# Syntheseproject_Elektronisch_Schema_2025.net
KiCad netlist of a schematic drawn in EasyEDA Pro
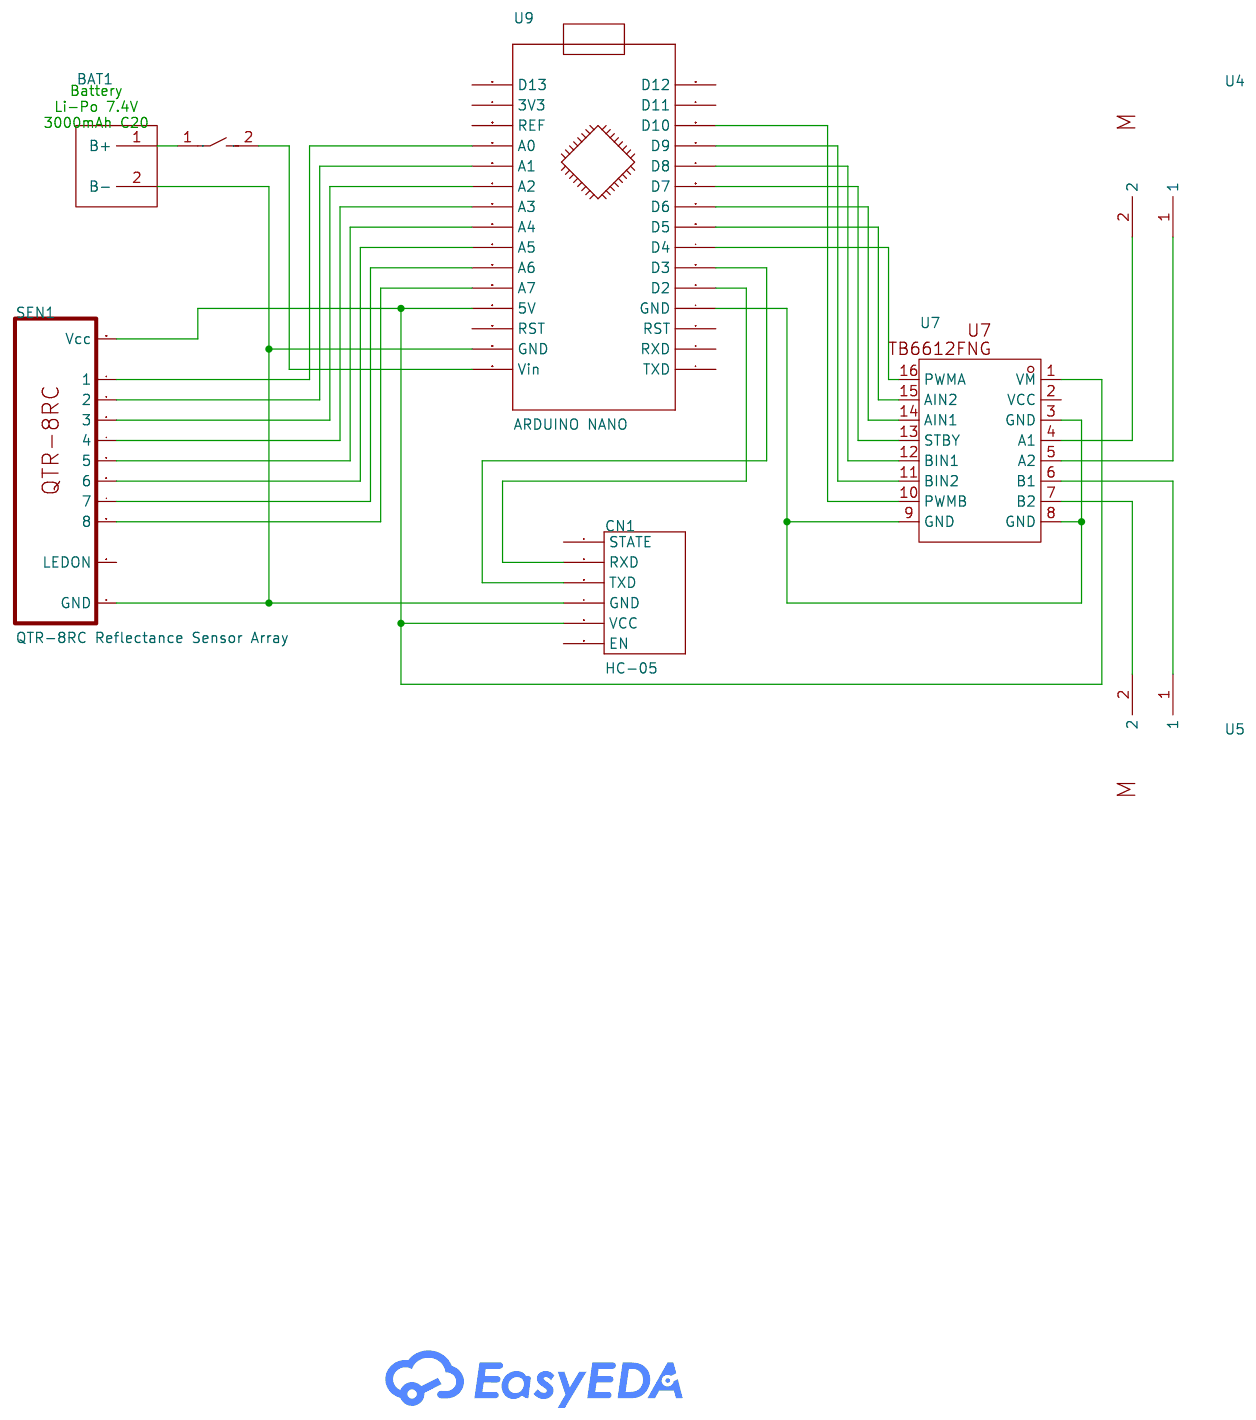
[diagram p0: schematic sheet]

(export (version "E")
  (design (tool "Eeschema 10.0.6"))
  (components
    (comp (ref "BAT1")
      (value "LiPo_7.4V_3000mAh_C20")
      (libsource (lib "easyedapro") (part "Battery_LiPo_7.4V_3000mAh"))
    )
    (comp (ref "CN1")
      (value "HC-05")
      (footprint "easyedapro:H6-2.54")
      (description "DIP-Black-Female-Header-VERT(6P)")
      (fields (field (name "Manufacturer Part") "F185-1106A1BSYC1"))
      (libsource (lib "easyedapro") (part "HC-05"))
    )
    (comp (ref "SEN1")
      (value "QTR-8RC Reflectance Sensor Array")
      (footprint "easyedapro:QTR-8X")
      (fields (field (name "Manufacturer") "Pololu"))
      (libsource (lib "easyedapro") (part "QTR-8RC Reflectance Sensor Array"))
    )
    (comp (ref "U4") (value "DC-MOTOR-GA12-N20") (libsource (lib "easyedapro") (part "DC-MOTOR-GA12-N20")))
    (comp (ref "U5") (value "DC-MOTOR-GA12-N20") (libsource (lib "easyedapro") (part "DC-MOTOR-GA12-N20")))
    (comp (ref "U7")
      (value "TB6612FNG SPARKFUN")
      (footprint "easyedapro:TB6612FNG")
      (fields (field (name "Manufacturer Part") "TB6612FNG"))
      (libsource (lib "easyedapro") (part "TB6612FNG SPARKFUN"))
    )
    (comp (ref "U8")
      (value "02-48-03-0004-00")
      (footprint "easyedapro:KEY-SMD_L6.0-W3.5-LS8.0-1")
      (libsource (lib "easyedapro") (part "02-48-03-0004-00"))
    )
    (comp (ref "U9")
      (value "ARDUINO NANO")
      (fields (field (name "Manufacturer Part") "?"))
      (libsource (lib "easyedapro") (part "ARDUINO NANO"))
    )
  )
  (nets
    (net (code "1") (name "Net-(BAT1-B+)") (class "Default")
      (node (ref "BAT1") (pin "1") (pinfunction "B+_1") (pintype "input"))
      (node (ref "U8") (pin "1") (pinfunction "1_1") (pintype "unspecified"))
    )
    (net (code "2") (name "Net-(BAT1-B-)") (class "Default")
      (node (ref "BAT1") (pin "2") (pinfunction "B-_2") (pintype "input"))
      (node (ref "CN1") (pin "4") (pinfunction "GND_4") (pintype "input"))
      (node (ref "SEN1") (pin "11") (pinfunction "GND_11") (pintype "unspecified"))
      (node (ref "U9") (pin "29") (pinfunction "GND_29") (pintype "unspecified"))
    )
    (net (code "3") (name "Net-(CN1-RXD)") (class "Default")
      (node (ref "CN1") (pin "2") (pinfunction "RXD_2") (pintype "input"))
      (node (ref "U9") (pin "5") (pinfunction "D2_5") (pintype "unspecified"))
    )
    (net (code "4") (name "Net-(CN1-TXD)") (class "Default")
      (node (ref "CN1") (pin "3") (pinfunction "TXD_3") (pintype "input"))
      (node (ref "U9") (pin "6") (pinfunction "D3_6") (pintype "unspecified"))
    )
    (net (code "5") (name "Net-(CN1-VCC)") (class "Default")
      (node (ref "CN1") (pin "5") (pinfunction "VCC_5") (pintype "input"))
      (node (ref "SEN1") (pin "10") (pinfunction "Vcc_10") (pintype "unspecified"))
      (node (ref "U7") (pin "1") (pinfunction "VM_1") (pintype "unspecified"))
      (node (ref "U9") (pin "27") (pinfunction "5V_27") (pintype "unspecified"))
    )
    (net (code "6") (name "Net-(U7-A1)") (class "Default")
      (node (ref "U4") (pin "2") (pinfunction "2_2") (pintype "unspecified"))
      (node (ref "U7") (pin "4") (pinfunction "A1_4") (pintype "unspecified"))
    )
    (net (code "7") (name "Net-(U7-A2)") (class "Default")
      (node (ref "U4") (pin "1") (pinfunction "1_1") (pintype "unspecified"))
      (node (ref "U7") (pin "5") (pinfunction "A2_5") (pintype "unspecified"))
    )
    (net (code "8") (name "Net-(U7-AIN1)") (class "Default")
      (node (ref "U7") (pin "14") (pinfunction "AIN1_14") (pintype "unspecified"))
      (node (ref "U9") (pin "9") (pinfunction "D6_9") (pintype "unspecified"))
    )
    (net (code "9") (name "Net-(U7-AIN2)") (class "Default")
      (node (ref "U7") (pin "15") (pinfunction "AIN2_15") (pintype "unspecified"))
      (node (ref "U9") (pin "8") (pinfunction "D5_8") (pintype "unspecified"))
    )
    (net (code "10") (name "Net-(U7-B1)") (class "Default")
      (node (ref "U5") (pin "1") (pinfunction "1_1") (pintype "unspecified"))
      (node (ref "U7") (pin "6") (pinfunction "B1_6") (pintype "unspecified"))
    )
    (net (code "11") (name "Net-(U7-B2)") (class "Default")
      (node (ref "U5") (pin "2") (pinfunction "2_2") (pintype "unspecified"))
      (node (ref "U7") (pin "7") (pinfunction "B2_7") (pintype "unspecified"))
    )
    (net (code "12") (name "Net-(U7-BIN1)") (class "Default")
      (node (ref "U7") (pin "12") (pinfunction "BIN1_12") (pintype "unspecified"))
      (node (ref "U9") (pin "11") (pinfunction "D8_11") (pintype "unspecified"))
    )
    (net (code "13") (name "Net-(U7-BIN2)") (class "Default")
      (node (ref "U7") (pin "11") (pinfunction "BIN2_11") (pintype "unspecified"))
      (node (ref "U9") (pin "12") (pinfunction "D9_12") (pintype "unspecified"))
    )
    (net (code "14") (name "Net-(U7-GND-Pad3)") (class "Default")
      (node (ref "U7") (pin "3") (pinfunction "GND_3") (pintype "unspecified"))
      (node (ref "U7") (pin "8") (pinfunction "GND_8") (pintype "unspecified"))
      (node (ref "U7") (pin "9") (pinfunction "GND_9") (pintype "unspecified"))
      (node (ref "U9") (pin "4") (pinfunction "GND_4") (pintype "unspecified"))
    )
    (net (code "15") (name "Net-(U7-PWMA)") (class "Default")
      (node (ref "U7") (pin "16") (pinfunction "PWMA_16") (pintype "unspecified"))
      (node (ref "U9") (pin "7") (pinfunction "D4_7") (pintype "unspecified"))
    )
    (net (code "16") (name "Net-(U7-PWMB)") (class "Default")
      (node (ref "U7") (pin "10") (pinfunction "PWMB_10") (pintype "unspecified"))
      (node (ref "U9") (pin "13") (pinfunction "D10_13") (pintype "unspecified"))
    )
    (net (code "17") (name "Net-(U7-STBY)") (class "Default")
      (node (ref "U7") (pin "13") (pinfunction "STBY_13") (pintype "unspecified"))
      (node (ref "U9") (pin "10") (pinfunction "D7_10") (pintype "unspecified"))
    )
    (net (code "18") (name "Net-(U9-A0)") (class "Default")
      (node (ref "SEN1") (pin "1") (pinfunction "1_1") (pintype "unspecified"))
      (node (ref "U9") (pin "19") (pinfunction "A0_19") (pintype "unspecified"))
    )
    (net (code "19") (name "Net-(U9-A1)") (class "Default")
      (node (ref "SEN1") (pin "2") (pinfunction "2_2") (pintype "unspecified"))
      (node (ref "U9") (pin "20") (pinfunction "A1_20") (pintype "unspecified"))
    )
    (net (code "20") (name "Net-(U9-A2)") (class "Default")
      (node (ref "SEN1") (pin "3") (pinfunction "3_3") (pintype "unspecified"))
      (node (ref "U9") (pin "21") (pinfunction "A2_21") (pintype "unspecified"))
    )
    (net (code "21") (name "Net-(U9-A3)") (class "Default")
      (node (ref "SEN1") (pin "4") (pinfunction "4_4") (pintype "unspecified"))
      (node (ref "U9") (pin "22") (pinfunction "A3_22") (pintype "unspecified"))
    )
    (net (code "22") (name "Net-(U9-A4)") (class "Default")
      (node (ref "SEN1") (pin "5") (pinfunction "5_5") (pintype "unspecified"))
      (node (ref "U9") (pin "23") (pinfunction "A4_23") (pintype "unspecified"))
    )
    (net (code "23") (name "Net-(U9-A5)") (class "Default")
      (node (ref "SEN1") (pin "6") (pinfunction "6_6") (pintype "unspecified"))
      (node (ref "U9") (pin "24") (pinfunction "A5_24") (pintype "unspecified"))
    )
    (net (code "24") (name "Net-(U9-A6)") (class "Default")
      (node (ref "SEN1") (pin "7") (pinfunction "7_7") (pintype "unspecified"))
      (node (ref "U9") (pin "25") (pinfunction "A6_25") (pintype "unspecified"))
    )
    (net (code "25") (name "Net-(U9-A7)") (class "Default")
      (node (ref "SEN1") (pin "8") (pinfunction "8_8") (pintype "unspecified"))
      (node (ref "U9") (pin "26") (pinfunction "A7_26") (pintype "unspecified"))
    )
    (net (code "26") (name "Net-(U9-Vin)") (class "Default")
      (node (ref "U8") (pin "2") (pinfunction "2_2") (pintype "unspecified"))
      (node (ref "U9") (pin "30") (pinfunction "Vin_30") (pintype "unspecified"))
    )
    (net (code "27") (name "unconnected-(CN1-EN-Pad6)") (class "Default")
      (node (ref "CN1") (pin "6") (pinfunction "EN_6") (pintype "input"))
    )
    (net (code "28") (name "unconnected-(CN1-STATE-Pad1)") (class "Default")
      (node (ref "CN1") (pin "1") (pinfunction "STATE_1") (pintype "input"))
    )
    (net (code "29") (name "unconnected-(SEN1-LEDON-Pad9)") (class "Default")
      (node (ref "SEN1") (pin "9") (pinfunction "LEDON_9") (pintype "unspecified"))
    )
    (net (code "30") (name "unconnected-(U7-VCC-Pad2)") (class "Default")
      (node (ref "U7") (pin "2") (pinfunction "VCC_2") (pintype "unspecified"))
    )
    (net (code "31") (name "unconnected-(U9-3V3-Pad17)") (class "Default")
      (node (ref "U9") (pin "17") (pinfunction "3V3_17") (pintype "unspecified"))
    )
    (net (code "32") (name "unconnected-(U9-D11-Pad14)") (class "Default")
      (node (ref "U9") (pin "14") (pinfunction "D11_14") (pintype "unspecified"))
    )
    (net (code "33") (name "unconnected-(U9-D12-Pad15)") (class "Default")
      (node (ref "U9") (pin "15") (pinfunction "D12_15") (pintype "unspecified"))
    )
    (net (code "34") (name "unconnected-(U9-D13-Pad16)") (class "Default")
      (node (ref "U9") (pin "16") (pinfunction "D13_16") (pintype "unspecified"))
    )
    (net (code "35") (name "unconnected-(U9-REF-Pad18)") (class "Default")
      (node (ref "U9") (pin "18") (pinfunction "REF_18") (pintype "unspecified"))
    )
    (net (code "36") (name "unconnected-(U9-RST-Pad3)") (class "Default")
      (node (ref "U9") (pin "3") (pinfunction "RST_3") (pintype "unspecified"))
    )
    (net (code "37") (name "unconnected-(U9-RST-Pad28)") (class "Default")
      (node (ref "U9") (pin "28") (pinfunction "RST_28") (pintype "unspecified"))
    )
    (net (code "38") (name "unconnected-(U9-RXD-Pad2)") (class "Default")
      (node (ref "U9") (pin "2") (pinfunction "RXD_2") (pintype "unspecified"))
    )
    (net (code "39") (name "unconnected-(U9-TXD-Pad1)") (class "Default")
      (node (ref "U9") (pin "1") (pinfunction "TXD_1") (pintype "unspecified"))
    )
  )
)
